# DC_Driver.net
KiCad netlist of a schematic drawn in EAGLE
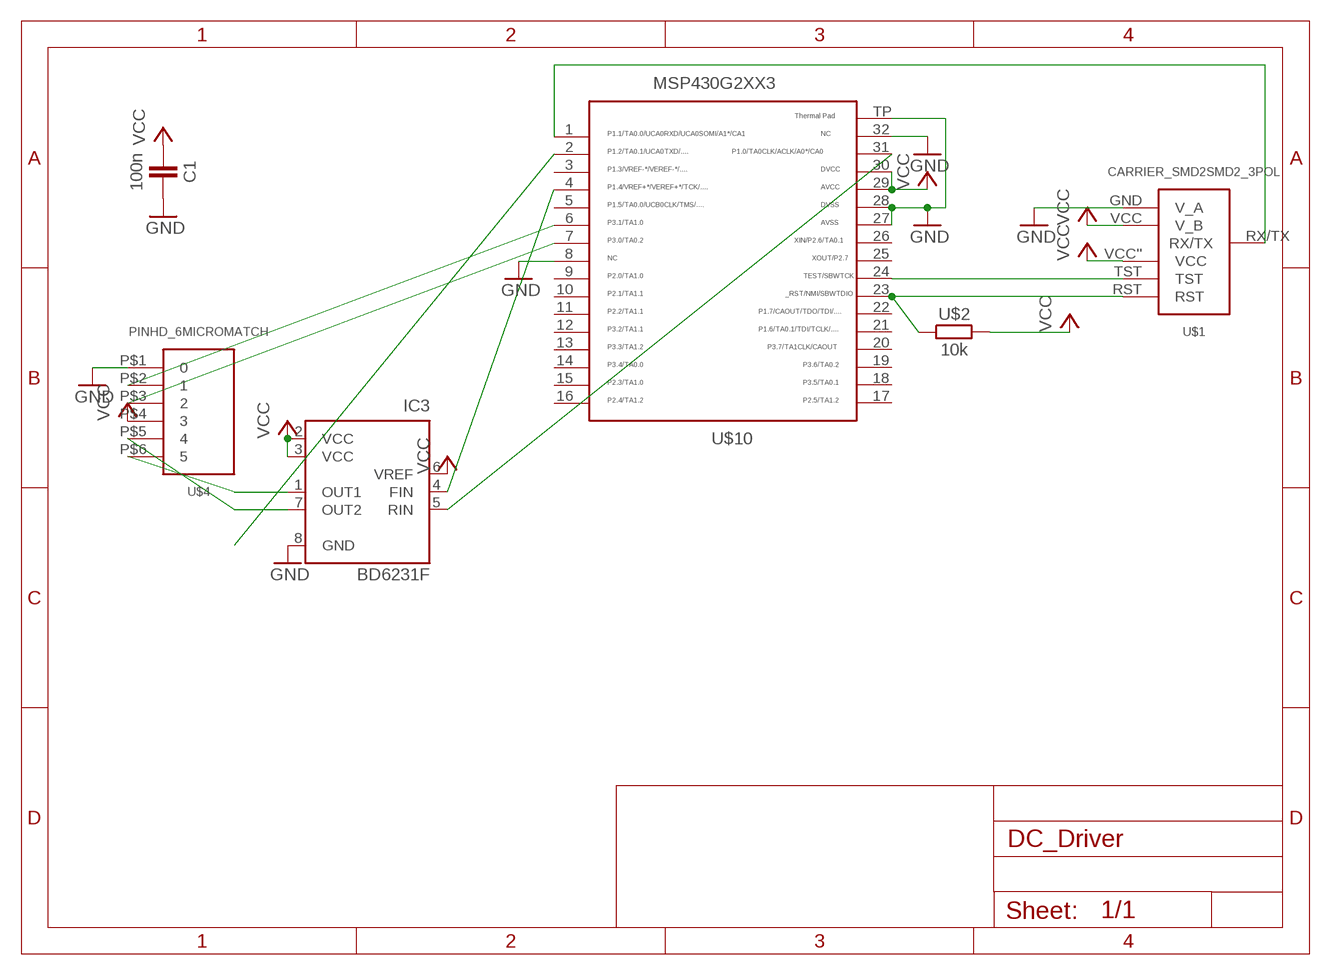
[diagram p0: schematic, sheet 1]

(export (version "E")
  (design (tool "Eeschema 10.0.6"))
  (components
    (comp (ref "C1")
      (value "100n")
      (footprint "eagle-import:603")
      (libsource (lib "eagle-import") (part "CAPACITOR"))
    )
    (comp (ref "IC3")
      (value "BD6231F")
      (footprint "eagle-import:SOP8")
      (fields (field (name "MPN") "BD6231F-E2"))
      (libsource (lib "eagle-import") (part "BD623F1"))
    )
    (comp (ref "U$1")
      (value "CARRIER_SMD2SMD2_3POL")
      (footprint "eagle-import:CARRIER_SMD2_3POL")
      (libsource (lib "eagle-import") (part "CARRIER_SMD2SMD2_3POL"))
    )
    (comp (ref "U$2")
      (value "10k")
      (footprint "eagle-import:603")
      (libsource (lib "eagle-import") (part "RESISTOR0603"))
    )
    (comp (ref "U$4")
      (value "PINHD_6MICROMATCH")
      (footprint "eagle-import:MICROMATCH6POL")
      (libsource (lib "eagle-import") (part "PINHD_6MICROMATCH"))
    )
    (comp (ref "U$10")
      (value "MSP430G2553")
      (footprint "eagle-import:QFN32")
      (libsource (lib "eagle-import") (part "MSP430G2553"))
    )
  )
  (nets
    (net (code "1") (name "GND") (class "Default")
      (node (ref "C1") (pin "2") (pinfunction "2_2") (pintype "passive"))
      (node (ref "IC3") (pin "8") (pinfunction "GND_8") (pintype "power_in"))
      (node (ref "U$1") (pin "GND") (pinfunction "V_A_GND") (pintype "bidirectional"))
      (node (ref "U$10") (pin "27") (pinfunction "27_27") (pintype "bidirectional"))
      (node (ref "U$10") (pin "28") (pinfunction "28_28") (pintype "bidirectional"))
      (node (ref "U$10") (pin "32") (pinfunction "32_32") (pintype "bidirectional"))
      (node (ref "U$10") (pin "8") (pinfunction "8_8") (pintype "bidirectional"))
      (node (ref "U$10") (pin "TP") (pinfunction "TP_TP") (pintype "bidirectional"))
      (node (ref "U$4") (pin "P$1") (pinfunction "0_P$1") (pintype "bidirectional"))
    )
    (net (code "2") (name "Net-(IC3-FIN)") (class "Default")
      (node (ref "IC3") (pin "4") (pinfunction "FIN_4") (pintype "input"))
      (node (ref "U$10") (pin "4") (pinfunction "4_4") (pintype "bidirectional"))
    )
    (net (code "3") (name "Net-(IC3-OUT1)") (class "Default")
      (node (ref "IC3") (pin "1") (pinfunction "OUT1_1") (pintype "output"))
      (node (ref "U$4") (pin "P$6") (pinfunction "5_P$6") (pintype "bidirectional"))
    )
    (net (code "4") (name "Net-(IC3-OUT2)") (class "Default")
      (node (ref "IC3") (pin "7") (pinfunction "OUT2_7") (pintype "output"))
      (node (ref "U$4") (pin "P$5") (pinfunction "4_P$5") (pintype "bidirectional"))
    )
    (net (code "5") (name "Net-(IC3-RIN)") (class "Default")
      (node (ref "IC3") (pin "5") (pinfunction "RIN_5") (pintype "input"))
      (node (ref "U$10") (pin "31") (pinfunction "31_31") (pintype "bidirectional"))
    )
    (net (code "6") (name "Net-(U$1-PadRST)") (class "Default")
      (node (ref "U$1") (pin "RST") (pinfunction "RST_RST") (pintype "bidirectional"))
      (node (ref "U$10") (pin "23") (pinfunction "23_23") (pintype "bidirectional"))
      (node (ref "U$2") (pin "1") (pinfunction "1_1") (pintype "passive"))
    )
    (net (code "7") (name "Net-(U$1-PadRX{slash}TX)") (class "Default")
      (node (ref "U$1") (pin "RX/TX") (pinfunction "RX/TX_RX/TX") (pintype "bidirectional"))
      (node (ref "U$10") (pin "1") (pinfunction "1_1") (pintype "bidirectional"))
    )
    (net (code "8") (name "Net-(U$1-PadTST)") (class "Default")
      (node (ref "U$1") (pin "TST") (pinfunction "TST_TST") (pintype "bidirectional"))
      (node (ref "U$10") (pin "24") (pinfunction "24_24") (pintype "bidirectional"))
    )
    (net (code "9") (name "Net-(U$4-1)") (class "Default")
      (node (ref "U$10") (pin "6") (pinfunction "6_6") (pintype "bidirectional"))
      (node (ref "U$4") (pin "P$2") (pinfunction "1_P$2") (pintype "bidirectional"))
    )
    (net (code "10") (name "Net-(U$4-2)") (class "Default")
      (node (ref "U$10") (pin "7") (pinfunction "7_7") (pintype "bidirectional"))
      (node (ref "U$4") (pin "P$3") (pinfunction "2_P$3") (pintype "bidirectional"))
    )
    (net (code "11") (name "VCC") (class "Default")
      (node (ref "C1") (pin "1") (pinfunction "1_1") (pintype "passive"))
      (node (ref "IC3") (pin "2") (pinfunction "VCC_2") (pintype "power_in"))
      (node (ref "IC3") (pin "3") (pinfunction "VCC_3") (pintype "power_in"))
      (node (ref "IC3") (pin "6") (pinfunction "VREF_6") (pintype "passive"))
      (node (ref "U$1") (pin "VCC") (pinfunction "V_B_VCC") (pintype "bidirectional"))
      (node (ref "U$1") (pin "VCC''") (pinfunction "VCC_VCC''") (pintype "bidirectional"))
      (node (ref "U$10") (pin "29") (pinfunction "29_29") (pintype "bidirectional"))
      (node (ref "U$10") (pin "30") (pinfunction "30_30") (pintype "bidirectional"))
      (node (ref "U$2") (pin "2") (pinfunction "2_2") (pintype "passive"))
      (node (ref "U$4") (pin "P$4") (pinfunction "3_P$4") (pintype "bidirectional"))
    )
    (net (code "12") (name "unconnected-(U$10-Pad2)") (class "Default")
      (node (ref "U$10") (pin "2") (pinfunction "2_2") (pintype "bidirectional"))
    )
    (net (code "13") (name "unconnected-(U$10-Pad3)") (class "Default")
      (node (ref "U$10") (pin "3") (pinfunction "3_3") (pintype "bidirectional"))
    )
    (net (code "14") (name "unconnected-(U$10-Pad5)") (class "Default")
      (node (ref "U$10") (pin "5") (pinfunction "5_5") (pintype "bidirectional"))
    )
    (net (code "15") (name "unconnected-(U$10-Pad9)") (class "Default")
      (node (ref "U$10") (pin "9") (pinfunction "9_9") (pintype "bidirectional"))
    )
    (net (code "16") (name "unconnected-(U$10-Pad10)") (class "Default")
      (node (ref "U$10") (pin "10") (pinfunction "10_10") (pintype "bidirectional"))
    )
    (net (code "17") (name "unconnected-(U$10-Pad11)") (class "Default")
      (node (ref "U$10") (pin "11") (pinfunction "11_11") (pintype "bidirectional"))
    )
    (net (code "18") (name "unconnected-(U$10-Pad12)") (class "Default")
      (node (ref "U$10") (pin "12") (pinfunction "12_12") (pintype "bidirectional"))
    )
    (net (code "19") (name "unconnected-(U$10-Pad13)") (class "Default")
      (node (ref "U$10") (pin "13") (pinfunction "13_13") (pintype "bidirectional"))
    )
    (net (code "20") (name "unconnected-(U$10-Pad14)") (class "Default")
      (node (ref "U$10") (pin "14") (pinfunction "14_14") (pintype "bidirectional"))
    )
    (net (code "21") (name "unconnected-(U$10-Pad15)") (class "Default")
      (node (ref "U$10") (pin "15") (pinfunction "15_15") (pintype "bidirectional"))
    )
    (net (code "22") (name "unconnected-(U$10-Pad16)") (class "Default")
      (node (ref "U$10") (pin "16") (pinfunction "16_16") (pintype "bidirectional"))
    )
    (net (code "23") (name "unconnected-(U$10-Pad17)") (class "Default")
      (node (ref "U$10") (pin "17") (pinfunction "17_17") (pintype "bidirectional"))
    )
    (net (code "24") (name "unconnected-(U$10-Pad18)") (class "Default")
      (node (ref "U$10") (pin "18") (pinfunction "18_18") (pintype "bidirectional"))
    )
    (net (code "25") (name "unconnected-(U$10-Pad19)") (class "Default")
      (node (ref "U$10") (pin "19") (pinfunction "19_19") (pintype "bidirectional"))
    )
    (net (code "26") (name "unconnected-(U$10-Pad20)") (class "Default")
      (node (ref "U$10") (pin "20") (pinfunction "20_20") (pintype "bidirectional"))
    )
    (net (code "27") (name "unconnected-(U$10-Pad21)") (class "Default")
      (node (ref "U$10") (pin "21") (pinfunction "21_21") (pintype "bidirectional"))
    )
    (net (code "28") (name "unconnected-(U$10-Pad22)") (class "Default")
      (node (ref "U$10") (pin "22") (pinfunction "22_22") (pintype "bidirectional"))
    )
    (net (code "29") (name "unconnected-(U$10-Pad25)") (class "Default")
      (node (ref "U$10") (pin "25") (pinfunction "25_25") (pintype "bidirectional"))
    )
    (net (code "30") (name "unconnected-(U$10-Pad26)") (class "Default")
      (node (ref "U$10") (pin "26") (pinfunction "26_26") (pintype "bidirectional"))
    )
  )
)
